# v1.net
KiCad netlist of a schematic drawn in EAGLE
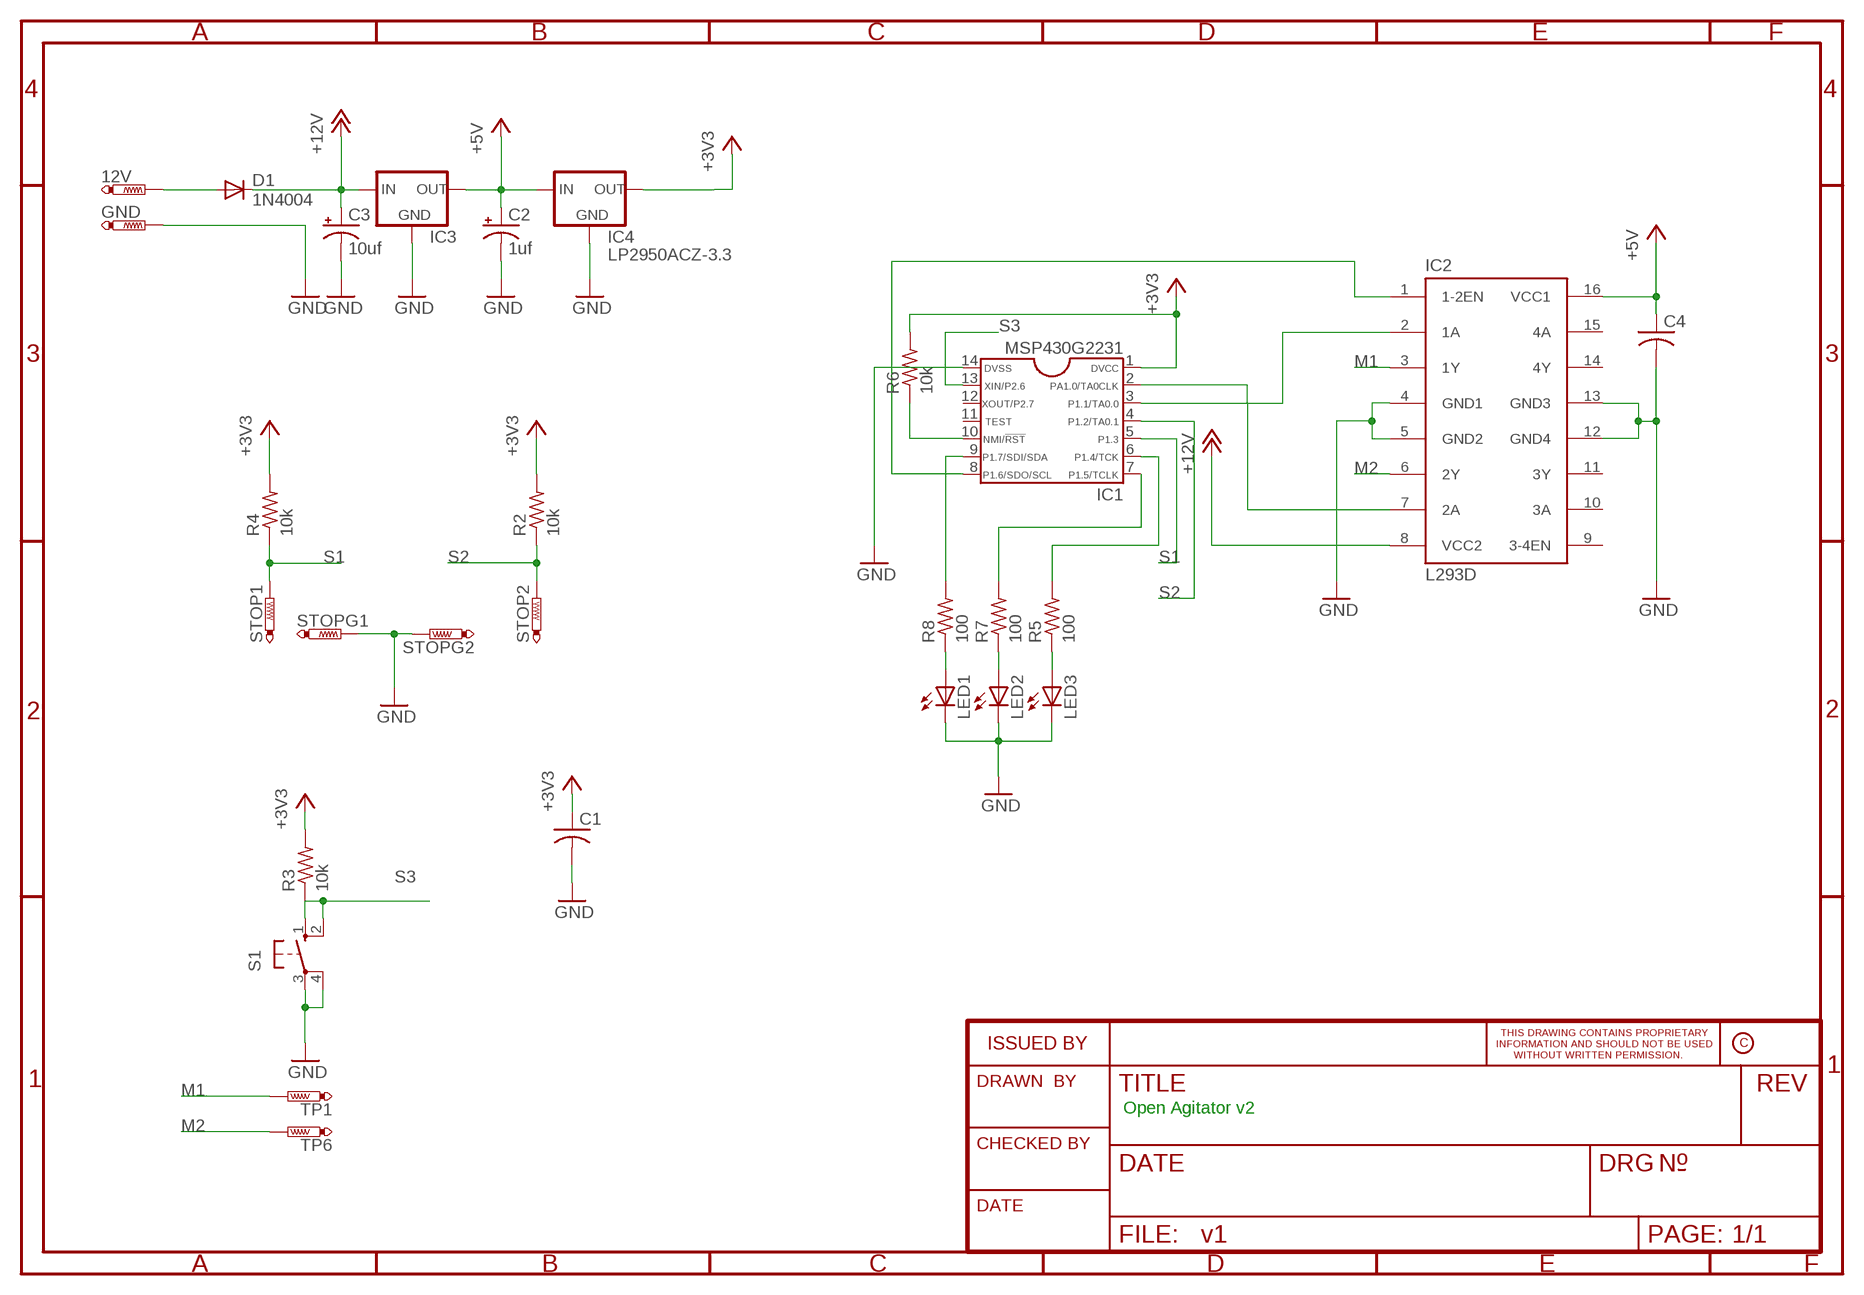
[diagram p0: schematic, sheet 1]

(export (version "E")
  (design (tool "Eeschema 10.0.6"))
  (components
    (comp (ref "12V")
      (value "PTR1PAD1-13Y")
      (footprint "eagle-import:P1-13Y")
      (libsource (lib "eagle-import") (part "PTR1PAD1-13Y"))
    )
    (comp (ref "C1")
      (value "CAP0805")
      (footprint "eagle-import:C0805")
      (libsource (lib "eagle-import") (part "CAP0805"))
    )
    (comp (ref "C2")
      (value "1uf")
      (footprint "eagle-import:E2,5-6E")
      (libsource (lib "eagle-import") (part "CPOL-USE2,5-6E"))
    )
    (comp (ref "C3")
      (value "10uf")
      (footprint "eagle-import:E2,5-6E")
      (libsource (lib "eagle-import") (part "CPOL-USE2,5-6E"))
    )
    (comp (ref "C4")
      (value "CAP0805")
      (footprint "eagle-import:C0805")
      (libsource (lib "eagle-import") (part "CAP0805"))
    )
    (comp (ref "D1")
      (value "1N4004")
      (footprint "eagle-import:DO41-10")
      (libsource (lib "eagle-import") (part "1N4004"))
    )
    (comp (ref "GND")
      (value "PTR1PAD1-13Y")
      (footprint "eagle-import:P1-13Y")
      (libsource (lib "eagle-import") (part "PTR1PAD1-13Y"))
    )
    (comp (ref "IC1")
      (value "MSP430G2231")
      (footprint "eagle-import:DIP14")
      (libsource (lib "eagle-import") (part "MSP430G2231"))
    )
    (comp (ref "IC2")
      (value "L293D")
      (footprint "eagle-import:DIL16")
      (libsource (lib "eagle-import") (part "L293D"))
    )
    (comp (ref "IC3")
      (value "V_REG_78XX-TO-220")
      (footprint "eagle-import:TO-220-ALT")
      (libsource (lib "eagle-import") (part "V_REG_78XX-TO-220"))
    )
    (comp (ref "IC4")
      (value "LP2950ACZ-3.3")
      (footprint "eagle-import:TO92")
      (libsource (lib "eagle-import") (part "LP2950?ACZ-3.3"))
    )
    (comp (ref "LED1")
      (value "LED5MM")
      (footprint "eagle-import:LED5MM")
      (libsource (lib "eagle-import") (part "LED5MM"))
    )
    (comp (ref "LED2")
      (value "LED5MM")
      (footprint "eagle-import:LED5MM")
      (libsource (lib "eagle-import") (part "LED5MM"))
    )
    (comp (ref "LED3")
      (value "LED5MM")
      (footprint "eagle-import:LED5MM")
      (libsource (lib "eagle-import") (part "LED5MM"))
    )
    (comp (ref "R2")
      (value "10k")
      (footprint "eagle-import:0207_10")
      (libsource (lib "eagle-import") (part "RESISTOR0207/10"))
    )
    (comp (ref "R3")
      (value "10k")
      (footprint "eagle-import:0207_7")
      (libsource (lib "eagle-import") (part "RESISTOR0207/7"))
    )
    (comp (ref "R4")
      (value "10k")
      (footprint "eagle-import:0207_7")
      (libsource (lib "eagle-import") (part "RESISTOR0207/7"))
    )
    (comp (ref "R5")
      (value "100")
      (footprint "eagle-import:0207_7")
      (libsource (lib "eagle-import") (part "RESISTOR0207/7"))
    )
    (comp (ref "R6")
      (value "10k")
      (footprint "eagle-import:0207_7")
      (libsource (lib "eagle-import") (part "RESISTOR0207/7"))
    )
    (comp (ref "R7")
      (value "100")
      (footprint "eagle-import:0207_7")
      (libsource (lib "eagle-import") (part "RESISTOR0207/7"))
    )
    (comp (ref "R8")
      (value "100")
      (footprint "eagle-import:0207_10")
      (libsource (lib "eagle-import") (part "RESISTOR0207/10"))
    )
    (comp (ref "S1")
      (value "10-XX")
      (footprint "eagle-import:B3F-10XX")
      (libsource (lib "eagle-import") (part "10-XX"))
    )
    (comp (ref "STOP1")
      (value "PTR1PAD1-13Y")
      (footprint "eagle-import:P1-13Y")
      (libsource (lib "eagle-import") (part "PTR1PAD1-13Y"))
    )
    (comp (ref "STOP2")
      (value "PTR1PAD1-13Y")
      (footprint "eagle-import:P1-13Y")
      (libsource (lib "eagle-import") (part "PTR1PAD1-13Y"))
    )
    (comp (ref "STOPG1")
      (value "PTR1PAD1-13Y")
      (footprint "eagle-import:P1-13Y")
      (libsource (lib "eagle-import") (part "PTR1PAD1-13Y"))
    )
    (comp (ref "STOPG2")
      (value "PTR1PAD1-13Y")
      (footprint "eagle-import:P1-13Y")
      (libsource (lib "eagle-import") (part "PTR1PAD1-13Y"))
    )
    (comp (ref "TP1")
      (value "PTR1PAD1-13Y")
      (footprint "eagle-import:P1-13Y")
      (libsource (lib "eagle-import") (part "PTR1PAD1-13Y"))
    )
    (comp (ref "TP6")
      (value "PTR1PAD1-13Y")
      (footprint "eagle-import:P1-13Y")
      (libsource (lib "eagle-import") (part "PTR1PAD1-13Y"))
    )
  )
  (nets
    (net (code "1") (name "+3V3") (class "Default")
      (node (ref "C1") (pin "1") (pinfunction "1_1") (pintype "passive"))
      (node (ref "IC1") (pin "1") (pinfunction "1_1") (pintype "passive"))
      (node (ref "IC4") (pin "1") (pinfunction "OUT_1") (pintype "passive"))
      (node (ref "R2") (pin "2") (pinfunction "2_2") (pintype "passive"))
      (node (ref "R3") (pin "2") (pinfunction "2_2") (pintype "passive"))
      (node (ref "R4") (pin "2") (pinfunction "2_2") (pintype "passive"))
      (node (ref "R6") (pin "2") (pinfunction "2_2") (pintype "passive"))
    )
    (net (code "2") (name "+5V") (class "Default")
      (node (ref "C2") (pin "+") (pinfunction "+_+") (pintype "passive"))
      (node (ref "C4") (pin "1") (pinfunction "1_1") (pintype "passive"))
      (node (ref "IC2") (pin "16") (pinfunction "VCC1_16") (pintype "power_in"))
      (node (ref "IC3") (pin "OUT") (pinfunction "OUT_OUT") (pintype "output"))
      (node (ref "IC4") (pin "3") (pinfunction "IN_3") (pintype "input"))
    )
    (net (code "3") (name "+12V") (class "Default")
      (node (ref "C3") (pin "+") (pinfunction "+_+") (pintype "passive"))
      (node (ref "D1") (pin "C") (pinfunction "C_C") (pintype "passive"))
      (node (ref "IC2") (pin "8") (pinfunction "VCC2_8") (pintype "power_in"))
      (node (ref "IC3") (pin "IN") (pinfunction "IN_IN") (pintype "input"))
    )
    (net (code "4") (name "/M1") (class "Default")
      (node (ref "IC2") (pin "3") (pinfunction "1Y_3") (pintype "output"))
      (node (ref "TP1") (pin "TP") (pinfunction "TP_TP") (pintype "input"))
    )
    (net (code "5") (name "/M2") (class "Default")
      (node (ref "IC2") (pin "6") (pinfunction "2Y_6") (pintype "output"))
      (node (ref "TP6") (pin "TP") (pinfunction "TP_TP") (pintype "input"))
    )
    (net (code "6") (name "/S1") (class "Default")
      (node (ref "IC1") (pin "5") (pinfunction "5_5") (pintype "passive"))
      (node (ref "R4") (pin "1") (pinfunction "1_1") (pintype "passive"))
      (node (ref "STOP1") (pin "TP") (pinfunction "TP_TP") (pintype "input"))
    )
    (net (code "7") (name "/S2") (class "Default")
      (node (ref "IC1") (pin "4") (pinfunction "4_4") (pintype "passive"))
      (node (ref "R2") (pin "1") (pinfunction "1_1") (pintype "passive"))
      (node (ref "STOP2") (pin "TP") (pinfunction "TP_TP") (pintype "input"))
    )
    (net (code "8") (name "/S3") (class "Default")
      (node (ref "IC1") (pin "13") (pinfunction "13_13") (pintype "passive"))
      (node (ref "R3") (pin "1") (pinfunction "1_1") (pintype "passive"))
      (node (ref "S1") (pin "1") (pinfunction "S_1") (pintype "passive"))
      (node (ref "S1") (pin "2") (pinfunction "S1_2") (pintype "passive"))
    )
    (net (code "9") (name "GND") (class "Default")
      (node (ref "C1") (pin "2") (pinfunction "2_2") (pintype "passive"))
      (node (ref "C2") (pin "-") (pinfunction "-_-") (pintype "passive"))
      (node (ref "C3") (pin "-") (pinfunction "-_-") (pintype "passive"))
      (node (ref "C4") (pin "2") (pinfunction "2_2") (pintype "passive"))
      (node (ref "GND") (pin "TP") (pinfunction "TP_TP") (pintype "input"))
      (node (ref "IC1") (pin "14") (pinfunction "14_14") (pintype "passive"))
      (node (ref "IC2") (pin "12") (pinfunction "GND4_12") (pintype "power_in"))
      (node (ref "IC2") (pin "13") (pinfunction "GND3_13") (pintype "power_in"))
      (node (ref "IC2") (pin "4") (pinfunction "GND1_4") (pintype "power_in"))
      (node (ref "IC2") (pin "5") (pinfunction "GND2_5") (pintype "power_in"))
      (node (ref "IC3") (pin "GND") (pinfunction "GND_GND") (pintype "input"))
      (node (ref "IC4") (pin "2") (pinfunction "GND_2") (pintype "input"))
      (node (ref "LED1") (pin "K") (pinfunction "C_K") (pintype "passive"))
      (node (ref "LED2") (pin "K") (pinfunction "C_K") (pintype "passive"))
      (node (ref "LED3") (pin "K") (pinfunction "C_K") (pintype "passive"))
      (node (ref "S1") (pin "3") (pinfunction "P_3") (pintype "passive"))
      (node (ref "S1") (pin "4") (pinfunction "P1_4") (pintype "passive"))
      (node (ref "STOPG1") (pin "TP") (pinfunction "TP_TP") (pintype "input"))
      (node (ref "STOPG2") (pin "TP") (pinfunction "TP_TP") (pintype "input"))
    )
    (net (code "10") (name "Net-(12V-PadTP)") (class "Default")
      (node (ref "12V") (pin "TP") (pinfunction "TP_TP") (pintype "input"))
      (node (ref "D1") (pin "A") (pinfunction "A_A") (pintype "passive"))
    )
    (net (code "11") (name "Net-(IC1-Pad6)") (class "Default")
      (node (ref "IC1") (pin "6") (pinfunction "6_6") (pintype "passive"))
      (node (ref "R5") (pin "2") (pinfunction "2_2") (pintype "passive"))
    )
    (net (code "12") (name "Net-(IC1-Pad7)") (class "Default")
      (node (ref "IC1") (pin "7") (pinfunction "7_7") (pintype "passive"))
      (node (ref "R7") (pin "2") (pinfunction "2_2") (pintype "passive"))
    )
    (net (code "13") (name "Net-(IC1-Pad9)") (class "Default")
      (node (ref "IC1") (pin "9") (pinfunction "9_9") (pintype "passive"))
      (node (ref "R8") (pin "2") (pinfunction "2_2") (pintype "passive"))
    )
    (net (code "14") (name "Net-(IC1-Pad10)") (class "Default")
      (node (ref "IC1") (pin "10") (pinfunction "10_10") (pintype "passive"))
      (node (ref "R6") (pin "1") (pinfunction "1_1") (pintype "passive"))
    )
    (net (code "15") (name "Net-(IC2-1-2EN)") (class "Default")
      (node (ref "IC1") (pin "8") (pinfunction "8_8") (pintype "passive"))
      (node (ref "IC2") (pin "1") (pinfunction "1-2EN_1") (pintype "input"))
    )
    (net (code "16") (name "Net-(IC2-1A)") (class "Default")
      (node (ref "IC1") (pin "3") (pinfunction "3_3") (pintype "passive"))
      (node (ref "IC2") (pin "2") (pinfunction "1A_2") (pintype "input"))
    )
    (net (code "17") (name "Net-(IC2-2A)") (class "Default")
      (node (ref "IC1") (pin "2") (pinfunction "2_2") (pintype "passive"))
      (node (ref "IC2") (pin "7") (pinfunction "2A_7") (pintype "input"))
    )
    (net (code "18") (name "Net-(LED1-PadA)") (class "Default")
      (node (ref "LED1") (pin "A") (pinfunction "A_A") (pintype "passive"))
      (node (ref "R8") (pin "1") (pinfunction "1_1") (pintype "passive"))
    )
    (net (code "19") (name "Net-(LED2-PadA)") (class "Default")
      (node (ref "LED2") (pin "A") (pinfunction "A_A") (pintype "passive"))
      (node (ref "R7") (pin "1") (pinfunction "1_1") (pintype "passive"))
    )
    (net (code "20") (name "Net-(LED3-PadA)") (class "Default")
      (node (ref "LED3") (pin "A") (pinfunction "A_A") (pintype "passive"))
      (node (ref "R5") (pin "1") (pinfunction "1_1") (pintype "passive"))
    )
    (net (code "21") (name "unconnected-(IC1-Pad11)") (class "Default")
      (node (ref "IC1") (pin "11") (pinfunction "11_11") (pintype "passive"))
    )
    (net (code "22") (name "unconnected-(IC1-Pad12)") (class "Default")
      (node (ref "IC1") (pin "12") (pinfunction "12_12") (pintype "passive"))
    )
    (net (code "23") (name "unconnected-(IC2-3-4EN-Pad9)") (class "Default")
      (node (ref "IC2") (pin "9") (pinfunction "3-4EN_9") (pintype "input"))
    )
    (net (code "24") (name "unconnected-(IC2-3A-Pad10)") (class "Default")
      (node (ref "IC2") (pin "10") (pinfunction "3A_10") (pintype "input"))
    )
    (net (code "25") (name "unconnected-(IC2-3Y-Pad11)") (class "Default")
      (node (ref "IC2") (pin "11") (pinfunction "3Y_11") (pintype "output"))
    )
    (net (code "26") (name "unconnected-(IC2-4A-Pad15)") (class "Default")
      (node (ref "IC2") (pin "15") (pinfunction "4A_15") (pintype "input"))
    )
    (net (code "27") (name "unconnected-(IC2-4Y-Pad14)") (class "Default")
      (node (ref "IC2") (pin "14") (pinfunction "4Y_14") (pintype "output"))
    )
  )
)
